# TCRT5000COM.net
KiCad netlist of a schematic drawn in Altium Designer
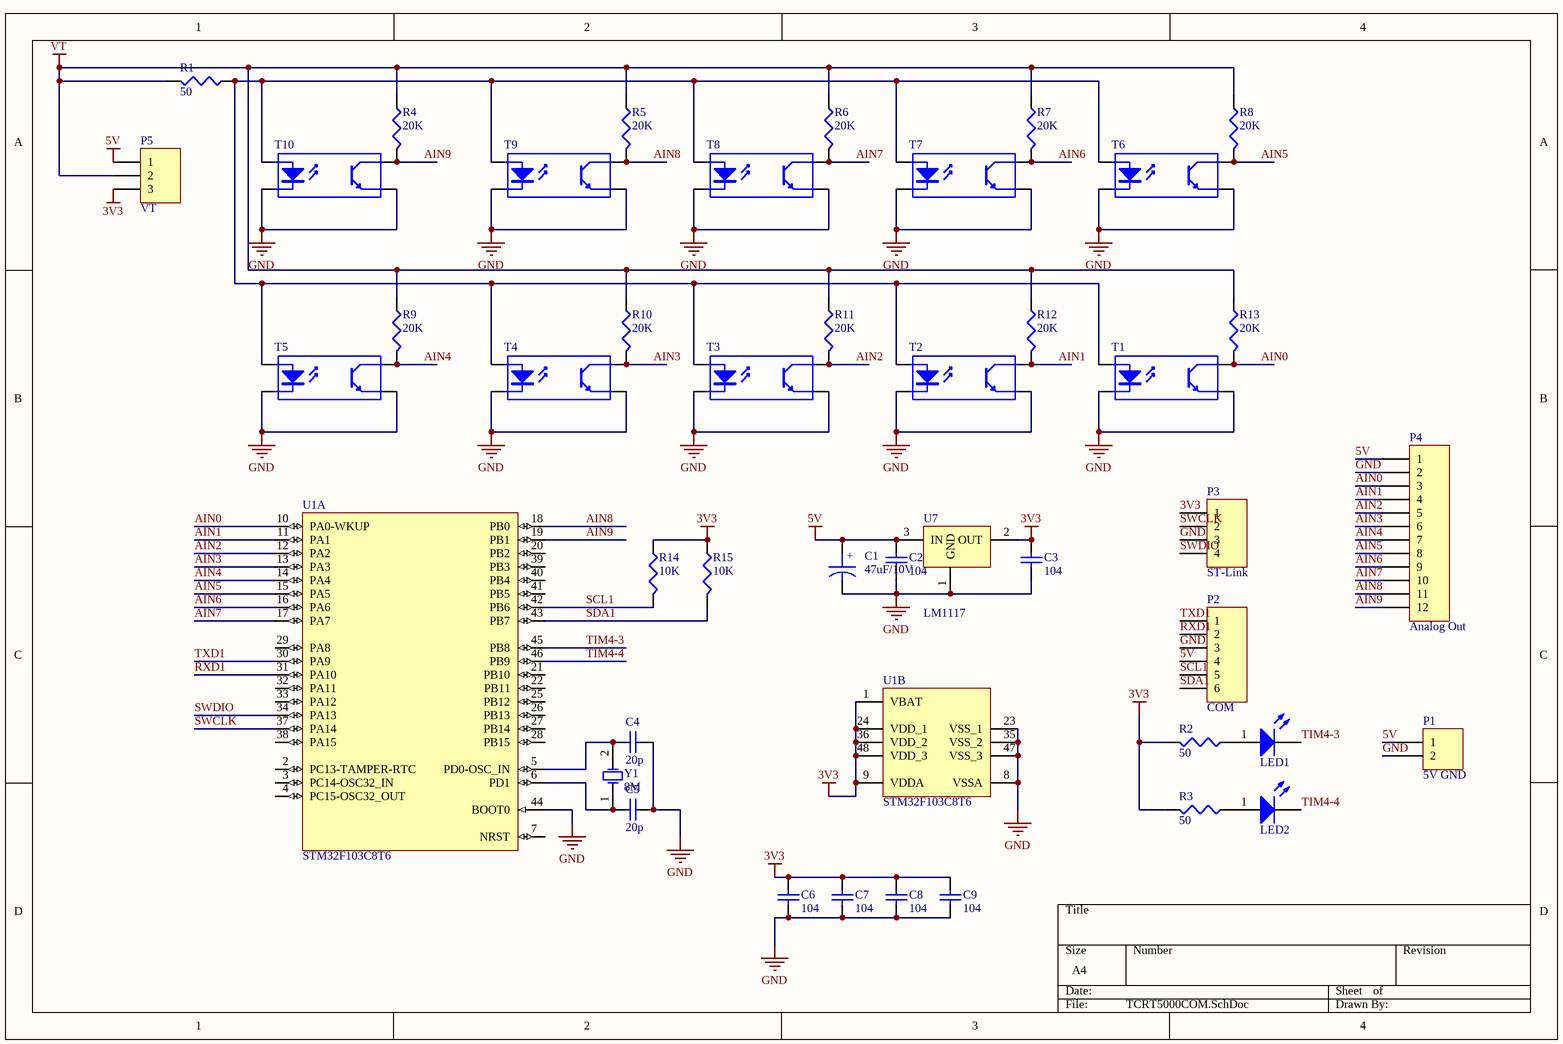
[diagram p0: TCRT5000COM.SchDoc]

(export (version "E")
  (design (tool "Eeschema 10.0.6"))
  (components
    (comp (ref "C1") (value "47uF/10V") (footprint "RB2") (libsource (lib "SmartHome") (part "CAP POL")))
    (comp (ref "C2")
      (value "104")
      (description "Capacitor")
      (fields (field (name "Comment") "Cap") (field (name "PUBLISHER") "Altium Limited"))
      (libsource (lib "Miscellaneous Devices") (part "Cap"))
    )
    (comp (ref "C3")
      (value "104")
      (description "Capacitor")
      (fields (field (name "Comment") "Cap") (field (name "PUBLISHER") "Altium Limited"))
      (libsource (lib "Miscellaneous Devices") (part "Cap"))
    )
    (comp (ref "C4")
      (value "20p")
      (footprint "0603")
      (description "Capacitor")
      (fields (field (name "PUBLISHER") "Altium Limited"))
      (libsource (lib "AMT149") (part "Cap"))
    )
    (comp (ref "C5")
      (value "20p")
      (footprint "0603")
      (description "Capacitor")
      (fields (field (name "PUBLISHER") "Altium Limited"))
      (libsource (lib "AMT149") (part "Cap"))
    )
    (comp (ref "C6")
      (value "104")
      (description "Capacitor")
      (fields (field (name "Comment") "Cap") (field (name "PUBLISHER") "Altium Limited"))
      (libsource (lib "Miscellaneous Devices") (part "Cap"))
    )
    (comp (ref "C7")
      (value "104")
      (description "Capacitor")
      (fields (field (name "Comment") "Cap") (field (name "PUBLISHER") "Altium Limited"))
      (libsource (lib "Miscellaneous Devices") (part "Cap"))
    )
    (comp (ref "C8")
      (value "104")
      (description "Capacitor")
      (fields (field (name "Comment") "Cap") (field (name "PUBLISHER") "Altium Limited"))
      (libsource (lib "Miscellaneous Devices") (part "Cap"))
    )
    (comp (ref "C9")
      (value "104")
      (description "Capacitor")
      (fields (field (name "Comment") "Cap") (field (name "PUBLISHER") "Altium Limited"))
      (libsource (lib "Miscellaneous Devices") (part "Cap"))
    )
    (comp (ref "LED1")
      (value "LED-white")
      (footprint "LED-white")
      (description "Typical INFRARED GaAs LED")
      (fields (field (name "PUBLISHER") "Altium Limited"))
      (libsource (lib "AMT149") (part "LED-white"))
    )
    (comp (ref "LED2")
      (value "LED-white")
      (footprint "LED-white")
      (description "Typical INFRARED GaAs LED")
      (fields (field (name "PUBLISHER") "Altium Limited"))
      (libsource (lib "AMT149") (part "LED-white"))
    )
    (comp (ref "P1")
      (value "5V GND")
      (footprint "SIP2-150")
      (description "Header, 2-Pin")
      (fields (field (name "PUBLISHER") "Altium Limited"))
      (libsource (lib "MainBoardV2") (part "Header 2"))
    )
    (comp (ref "P2")
      (value "COM")
      (footprint "HDR1X6")
      (description "Header, 6-Pin")
      (fields (field (name "PUBLISHER") "Altium Limited"))
      (libsource (lib "Miscellaneous Connectors") (part "Header 6"))
    )
    (comp (ref "P3")
      (value "ST-Link")
      (footprint "HDR1X4")
      (description "Header, 4-Pin")
      (fields (field (name "PUBLISHER") "Altium Limited"))
      (libsource (lib "Miscellaneous Connectors") (part "Header 4"))
    )
    (comp (ref "P4")
      (value "Analog Out")
      (footprint "HDR1X12")
      (description "Header, 12-Pin")
      (fields (field (name "PUBLISHER") "Altium Limited"))
      (libsource (lib "MainBoardV2") (part "Header 12"))
    )
    (comp (ref "P5")
      (value "VT")
      (footprint "HDR1X3")
      (description "Header, 3-Pin")
      (fields (field (name "PUBLISHER") "Altium Limited"))
      (libsource (lib "MainBoardV2") (part "Header 3"))
    )
    (comp (ref "R1")
      (value "50")
      (description "Resistor")
      (fields (field (name "Comment") "Res3") (field (name "PUBLISHER") "Altium Limited"))
      (libsource (lib "Miscellaneous Devices") (part "Res3"))
    )
    (comp (ref "R2")
      (value "50")
      (description "Resistor")
      (fields (field (name "Comment") "Res3") (field (name "PUBLISHER") "Altium Limited"))
      (libsource (lib "Miscellaneous Devices") (part "Res3"))
    )
    (comp (ref "R3")
      (value "50")
      (description "Resistor")
      (fields (field (name "Comment") "Res3") (field (name "PUBLISHER") "Altium Limited"))
      (libsource (lib "Miscellaneous Devices") (part "Res3"))
    )
    (comp (ref "R4")
      (value "20K")
      (description "Resistor")
      (fields (field (name "Comment") "Res3") (field (name "PUBLISHER") "Altium Limited"))
      (libsource (lib "Miscellaneous Devices") (part "Res3"))
    )
    (comp (ref "R5")
      (value "20K")
      (description "Resistor")
      (fields (field (name "Comment") "Res3") (field (name "PUBLISHER") "Altium Limited"))
      (libsource (lib "Miscellaneous Devices") (part "Res3"))
    )
    (comp (ref "R6")
      (value "20K")
      (description "Resistor")
      (fields (field (name "Comment") "Res3") (field (name "PUBLISHER") "Altium Limited"))
      (libsource (lib "Miscellaneous Devices") (part "Res3"))
    )
    (comp (ref "R7")
      (value "20K")
      (description "Resistor")
      (fields (field (name "Comment") "Res3") (field (name "PUBLISHER") "Altium Limited"))
      (libsource (lib "Miscellaneous Devices") (part "Res3"))
    )
    (comp (ref "R8")
      (value "20K")
      (description "Resistor")
      (fields (field (name "Comment") "Res3") (field (name "PUBLISHER") "Altium Limited"))
      (libsource (lib "Miscellaneous Devices") (part "Res3"))
    )
    (comp (ref "R9")
      (value "20K")
      (description "Resistor")
      (fields (field (name "Comment") "Res3") (field (name "PUBLISHER") "Altium Limited"))
      (libsource (lib "Miscellaneous Devices") (part "Res3"))
    )
    (comp (ref "R10")
      (value "20K")
      (description "Resistor")
      (fields (field (name "Comment") "Res3") (field (name "PUBLISHER") "Altium Limited"))
      (libsource (lib "Miscellaneous Devices") (part "Res3"))
    )
    (comp (ref "R11")
      (value "20K")
      (description "Resistor")
      (fields (field (name "Comment") "Res3") (field (name "PUBLISHER") "Altium Limited"))
      (libsource (lib "Miscellaneous Devices") (part "Res3"))
    )
    (comp (ref "R12")
      (value "20K")
      (description "Resistor")
      (fields (field (name "Comment") "Res3") (field (name "PUBLISHER") "Altium Limited"))
      (libsource (lib "Miscellaneous Devices") (part "Res3"))
    )
    (comp (ref "R13")
      (value "20K")
      (description "Resistor")
      (fields (field (name "Comment") "Res3") (field (name "PUBLISHER") "Altium Limited"))
      (libsource (lib "Miscellaneous Devices") (part "Res3"))
    )
    (comp (ref "R14")
      (value "10K")
      (description "Resistor")
      (fields (field (name "Comment") "Res3") (field (name "PUBLISHER") "Altium Limited"))
      (libsource (lib "Miscellaneous Devices") (part "Res3"))
    )
    (comp (ref "R15")
      (value "10K")
      (description "Resistor")
      (fields (field (name "Comment") "Res3") (field (name "PUBLISHER") "Altium Limited"))
      (libsource (lib "Miscellaneous Devices") (part "Res3"))
    )
    (comp (ref "T1")
      (value "Optoisolator1")
      (footprint "TCRT5000")
      (description "4-Pin Phototransistor Optocoupler")
      (fields (field (name "PUBLISHER") "Altium Limited"))
      (libsource (lib "Miscellaneous Devices") (part "Optoisolator1"))
    )
    (comp (ref "T2")
      (value "Optoisolator1")
      (footprint "TCRT5000")
      (description "4-Pin Phototransistor Optocoupler")
      (fields (field (name "PUBLISHER") "Altium Limited"))
      (libsource (lib "Miscellaneous Devices") (part "Optoisolator1"))
    )
    (comp (ref "T3")
      (value "Optoisolator1")
      (footprint "TCRT5000")
      (description "4-Pin Phototransistor Optocoupler")
      (fields (field (name "PUBLISHER") "Altium Limited"))
      (libsource (lib "Miscellaneous Devices") (part "Optoisolator1"))
    )
    (comp (ref "T4")
      (value "Optoisolator1")
      (footprint "TCRT5000")
      (description "4-Pin Phototransistor Optocoupler")
      (fields (field (name "PUBLISHER") "Altium Limited"))
      (libsource (lib "Miscellaneous Devices") (part "Optoisolator1"))
    )
    (comp (ref "T5")
      (value "Optoisolator1")
      (footprint "TCRT5000")
      (description "4-Pin Phototransistor Optocoupler")
      (fields (field (name "PUBLISHER") "Altium Limited"))
      (libsource (lib "Miscellaneous Devices") (part "Optoisolator1"))
    )
    (comp (ref "T6")
      (value "Optoisolator1")
      (footprint "TCRT5000")
      (description "4-Pin Phototransistor Optocoupler")
      (fields (field (name "PUBLISHER") "Altium Limited"))
      (libsource (lib "Miscellaneous Devices") (part "Optoisolator1"))
    )
    (comp (ref "T7")
      (value "Optoisolator1")
      (footprint "TCRT5000")
      (description "4-Pin Phototransistor Optocoupler")
      (fields (field (name "PUBLISHER") "Altium Limited"))
      (libsource (lib "Miscellaneous Devices") (part "Optoisolator1"))
    )
    (comp (ref "T8")
      (value "Optoisolator1")
      (footprint "TCRT5000")
      (description "4-Pin Phototransistor Optocoupler")
      (fields (field (name "PUBLISHER") "Altium Limited"))
      (libsource (lib "Miscellaneous Devices") (part "Optoisolator1"))
    )
    (comp (ref "T9")
      (value "Optoisolator1")
      (footprint "TCRT5000")
      (description "4-Pin Phototransistor Optocoupler")
      (fields (field (name "PUBLISHER") "Altium Limited"))
      (libsource (lib "Miscellaneous Devices") (part "Optoisolator1"))
    )
    (comp (ref "T10")
      (value "Optoisolator1")
      (footprint "TCRT5000")
      (description "4-Pin Phototransistor Optocoupler")
      (fields (field (name "PUBLISHER") "Altium Limited"))
      (libsource (lib "Miscellaneous Devices") (part "Optoisolator1"))
    )
    (comp (ref "U1")
      (value "STM32F103C8T6")
      (footprint "QUAD48")
      (libsource (lib "AMT149") (part "STM32F103C8T6"))
    )
    (comp (ref "U7") (value "LM1117") (footprint "SPP3") (libsource (lib "*") (part "LM1117")))
    (comp (ref "Y1")
      (value "8M")
      (footprint "XTAL1")
      (description "Crystal Oscillator")
      (fields (field (name "PUBLISHER") "Altium Limited"))
      (libsource (lib "AMT149") (part "XTAL"))
    )
  )
  (nets
    (net (code "1") (name "/AIN0") (class "Default")
      (node (ref "P4") (pin "3") (pinfunction "3_3") (pintype "passive"))
      (node (ref "R13") (pin "2") (pinfunction "2_2") (pintype "passive"))
      (node (ref "T1") (pin "4") (pinfunction "C_4") (pintype "passive"))
      (node (ref "U1") (pin "10") (pinfunction "PA0-WKUP_10") (pintype "bidirectional"))
    )
    (net (code "2") (name "/AIN1") (class "Default")
      (node (ref "P4") (pin "4") (pinfunction "4_4") (pintype "passive"))
      (node (ref "R12") (pin "2") (pinfunction "2_2") (pintype "passive"))
      (node (ref "T2") (pin "4") (pinfunction "C_4") (pintype "passive"))
      (node (ref "U1") (pin "11") (pinfunction "PA1_11") (pintype "bidirectional"))
    )
    (net (code "3") (name "/AIN2") (class "Default")
      (node (ref "P4") (pin "5") (pinfunction "5_5") (pintype "passive"))
      (node (ref "R11") (pin "2") (pinfunction "2_2") (pintype "passive"))
      (node (ref "T3") (pin "4") (pinfunction "C_4") (pintype "passive"))
      (node (ref "U1") (pin "12") (pinfunction "PA2_12") (pintype "bidirectional"))
    )
    (net (code "4") (name "/AIN3") (class "Default")
      (node (ref "P4") (pin "6") (pinfunction "6_6") (pintype "passive"))
      (node (ref "R10") (pin "2") (pinfunction "2_2") (pintype "passive"))
      (node (ref "T4") (pin "4") (pinfunction "C_4") (pintype "passive"))
      (node (ref "U1") (pin "13") (pinfunction "PA3_13") (pintype "bidirectional"))
    )
    (net (code "5") (name "/AIN4") (class "Default")
      (node (ref "P4") (pin "7") (pinfunction "7_7") (pintype "passive"))
      (node (ref "R9") (pin "2") (pinfunction "2_2") (pintype "passive"))
      (node (ref "T5") (pin "4") (pinfunction "C_4") (pintype "passive"))
      (node (ref "U1") (pin "14") (pinfunction "PA4_14") (pintype "bidirectional"))
    )
    (net (code "6") (name "/AIN5") (class "Default")
      (node (ref "P4") (pin "8") (pinfunction "8_8") (pintype "passive"))
      (node (ref "R8") (pin "2") (pinfunction "2_2") (pintype "passive"))
      (node (ref "T6") (pin "4") (pinfunction "C_4") (pintype "passive"))
      (node (ref "U1") (pin "15") (pinfunction "PA5_15") (pintype "bidirectional"))
    )
    (net (code "7") (name "/AIN6") (class "Default")
      (node (ref "P4") (pin "9") (pinfunction "9_9") (pintype "passive"))
      (node (ref "R7") (pin "2") (pinfunction "2_2") (pintype "passive"))
      (node (ref "T7") (pin "4") (pinfunction "C_4") (pintype "passive"))
      (node (ref "U1") (pin "16") (pinfunction "PA6_16") (pintype "bidirectional"))
    )
    (net (code "8") (name "/AIN7") (class "Default")
      (node (ref "P4") (pin "10") (pinfunction "10_10") (pintype "passive"))
      (node (ref "R6") (pin "2") (pinfunction "2_2") (pintype "passive"))
      (node (ref "T8") (pin "4") (pinfunction "C_4") (pintype "passive"))
      (node (ref "U1") (pin "17") (pinfunction "PA7_17") (pintype "bidirectional"))
    )
    (net (code "9") (name "/AIN8") (class "Default")
      (node (ref "P4") (pin "11") (pinfunction "11_11") (pintype "passive"))
      (node (ref "R5") (pin "2") (pinfunction "2_2") (pintype "passive"))
      (node (ref "T9") (pin "4") (pinfunction "C_4") (pintype "passive"))
      (node (ref "U1") (pin "18") (pinfunction "PB0_18") (pintype "bidirectional"))
    )
    (net (code "10") (name "/AIN9") (class "Default")
      (node (ref "P4") (pin "12") (pinfunction "12_12") (pintype "passive"))
      (node (ref "R4") (pin "2") (pinfunction "2_2") (pintype "passive"))
      (node (ref "T10") (pin "4") (pinfunction "C_4") (pintype "passive"))
      (node (ref "U1") (pin "19") (pinfunction "PB1_19") (pintype "bidirectional"))
    )
    (net (code "11") (name "/RXD1") (class "Default")
      (node (ref "P2") (pin "2") (pinfunction "2_2") (pintype "passive"))
      (node (ref "U1") (pin "31") (pinfunction "PA10_31") (pintype "bidirectional"))
    )
    (net (code "12") (name "/SCL1") (class "Default")
      (node (ref "P2") (pin "5") (pinfunction "5_5") (pintype "passive"))
      (node (ref "R14") (pin "2") (pinfunction "2_2") (pintype "passive"))
      (node (ref "U1") (pin "42") (pinfunction "PB6_42") (pintype "bidirectional"))
    )
    (net (code "13") (name "/SDA1") (class "Default")
      (node (ref "P2") (pin "6") (pinfunction "6_6") (pintype "passive"))
      (node (ref "R15") (pin "2") (pinfunction "2_2") (pintype "passive"))
      (node (ref "U1") (pin "43") (pinfunction "PB7_43") (pintype "bidirectional"))
    )
    (net (code "14") (name "/SWCLK") (class "Default")
      (node (ref "P3") (pin "2") (pinfunction "2_2") (pintype "passive"))
      (node (ref "U1") (pin "37") (pinfunction "PA14_37") (pintype "bidirectional"))
    )
    (net (code "15") (name "/SWDIO") (class "Default")
      (node (ref "P3") (pin "4") (pinfunction "4_4") (pintype "passive"))
      (node (ref "U1") (pin "34") (pinfunction "PA13_34") (pintype "bidirectional"))
    )
    (net (code "16") (name "/TIM4-3") (class "Default")
      (node (ref "LED1") (pin "2") (pinfunction "K_2") (pintype "passive"))
      (node (ref "U1") (pin "45") (pinfunction "PB8_45") (pintype "bidirectional"))
    )
    (net (code "17") (name "/TIM4-4") (class "Default")
      (node (ref "LED2") (pin "2") (pinfunction "K_2") (pintype "passive"))
      (node (ref "U1") (pin "46") (pinfunction "PB9_46") (pintype "bidirectional"))
    )
    (net (code "18") (name "/TXD1") (class "Default")
      (node (ref "P2") (pin "1") (pinfunction "1_1") (pintype "passive"))
      (node (ref "U1") (pin "30") (pinfunction "PA9_30") (pintype "bidirectional"))
    )
    (net (code "19") (name "3V3") (class "Default")
      (node (ref "C3") (pin "2") (pinfunction "2_2") (pintype "passive"))
      (node (ref "C6") (pin "2") (pinfunction "2_2") (pintype "passive"))
      (node (ref "C7") (pin "2") (pinfunction "2_2") (pintype "passive"))
      (node (ref "C8") (pin "2") (pinfunction "2_2") (pintype "passive"))
      (node (ref "C9") (pin "2") (pinfunction "2_2") (pintype "passive"))
      (node (ref "P3") (pin "1") (pinfunction "1_1") (pintype "passive"))
      (node (ref "P5") (pin "3") (pinfunction "3_3") (pintype "passive"))
      (node (ref "R14") (pin "1") (pinfunction "1_1") (pintype "passive"))
      (node (ref "R15") (pin "1") (pinfunction "1_1") (pintype "passive"))
      (node (ref "R2") (pin "2") (pinfunction "2_2") (pintype "passive"))
      (node (ref "R3") (pin "2") (pinfunction "2_2") (pintype "passive"))
      (node (ref "U1") (pin "1") (pinfunction "VBAT_1") (pintype "power_in"))
      (node (ref "U1") (pin "24") (pinfunction "VDD_1_24") (pintype "power_in"))
      (node (ref "U1") (pin "36") (pinfunction "VDD_2_36") (pintype "power_in"))
      (node (ref "U1") (pin "48") (pinfunction "VDD_3_48") (pintype "power_in"))
      (node (ref "U1") (pin "9") (pinfunction "VDDA_9") (pintype "power_in"))
      (node (ref "U7") (pin "2") (pinfunction "OUT_2") (pintype "passive"))
    )
    (net (code "20") (name "5V") (class "Default")
      (node (ref "C1") (pin "1") (pinfunction "1_1") (pintype "passive"))
      (node (ref "C2") (pin "2") (pinfunction "2_2") (pintype "passive"))
      (node (ref "P1") (pin "1") (pinfunction "1_1") (pintype "passive"))
      (node (ref "P2") (pin "4") (pinfunction "4_4") (pintype "passive"))
      (node (ref "P4") (pin "1") (pinfunction "1_1") (pintype "passive"))
      (node (ref "P5") (pin "1") (pinfunction "1_1") (pintype "passive"))
      (node (ref "U7") (pin "3") (pinfunction "IN_3") (pintype "passive"))
    )
    (net (code "21") (name "GND") (class "Default")
      (node (ref "C1") (pin "2") (pinfunction "2_2") (pintype "passive"))
      (node (ref "C2") (pin "1") (pinfunction "1_1") (pintype "passive"))
      (node (ref "C3") (pin "1") (pinfunction "1_1") (pintype "passive"))
      (node (ref "C4") (pin "2") (pinfunction "2_2") (pintype "passive"))
      (node (ref "C5") (pin "2") (pinfunction "2_2") (pintype "passive"))
      (node (ref "C6") (pin "1") (pinfunction "1_1") (pintype "passive"))
      (node (ref "C7") (pin "1") (pinfunction "1_1") (pintype "passive"))
      (node (ref "C8") (pin "1") (pinfunction "1_1") (pintype "passive"))
      (node (ref "C9") (pin "1") (pinfunction "1_1") (pintype "passive"))
      (node (ref "P1") (pin "2") (pinfunction "2_2") (pintype "passive"))
      (node (ref "P2") (pin "3") (pinfunction "3_3") (pintype "passive"))
      (node (ref "P3") (pin "3") (pinfunction "3_3") (pintype "passive"))
      (node (ref "P4") (pin "2") (pinfunction "2_2") (pintype "passive"))
      (node (ref "T1") (pin "2") (pinfunction "K_2") (pintype "passive"))
      (node (ref "T1") (pin "3") (pinfunction "E_3") (pintype "passive"))
      (node (ref "T10") (pin "2") (pinfunction "K_2") (pintype "passive"))
      (node (ref "T10") (pin "3") (pinfunction "E_3") (pintype "passive"))
      (node (ref "T2") (pin "2") (pinfunction "K_2") (pintype "passive"))
      (node (ref "T2") (pin "3") (pinfunction "E_3") (pintype "passive"))
      (node (ref "T3") (pin "2") (pinfunction "K_2") (pintype "passive"))
      (node (ref "T3") (pin "3") (pinfunction "E_3") (pintype "passive"))
      (node (ref "T4") (pin "2") (pinfunction "K_2") (pintype "passive"))
      (node (ref "T4") (pin "3") (pinfunction "E_3") (pintype "passive"))
      (node (ref "T5") (pin "2") (pinfunction "K_2") (pintype "passive"))
      (node (ref "T5") (pin "3") (pinfunction "E_3") (pintype "passive"))
      (node (ref "T6") (pin "2") (pinfunction "K_2") (pintype "passive"))
      (node (ref "T6") (pin "3") (pinfunction "E_3") (pintype "passive"))
      (node (ref "T7") (pin "2") (pinfunction "K_2") (pintype "passive"))
      (node (ref "T7") (pin "3") (pinfunction "E_3") (pintype "passive"))
      (node (ref "T8") (pin "2") (pinfunction "K_2") (pintype "passive"))
      (node (ref "T8") (pin "3") (pinfunction "E_3") (pintype "passive"))
      (node (ref "T9") (pin "2") (pinfunction "K_2") (pintype "passive"))
      (node (ref "T9") (pin "3") (pinfunction "E_3") (pintype "passive"))
      (node (ref "U1") (pin "23") (pinfunction "VSS_1_23") (pintype "power_in"))
      (node (ref "U1") (pin "35") (pinfunction "VSS_2_35") (pintype "power_in"))
      (node (ref "U1") (pin "44") (pinfunction "BOOT0_44") (pintype "input"))
      (node (ref "U1") (pin "47") (pinfunction "VSS_3_47") (pintype "power_in"))
      (node (ref "U1") (pin "8") (pinfunction "VSSA_8") (pintype "power_in"))
      (node (ref "U7") (pin "1") (pinfunction "GND_1") (pintype "passive"))
    )
    (net (code "22") (name "Net-(LED1-A)") (class "Default")
      (node (ref "LED1") (pin "1") (pinfunction "A_1") (pintype "passive"))
      (node (ref "R2") (pin "1") (pinfunction "1_1") (pintype "passive"))
    )
    (net (code "23") (name "Net-(LED2-A)") (class "Default")
      (node (ref "LED2") (pin "1") (pinfunction "A_1") (pintype "passive"))
      (node (ref "R3") (pin "1") (pinfunction "1_1") (pintype "passive"))
    )
    (net (code "24") (name "Net-(T1-A)") (class "Default")
      (node (ref "R1") (pin "1") (pinfunction "1_1") (pintype "passive"))
      (node (ref "T1") (pin "1") (pinfunction "A_1") (pintype "passive"))
      (node (ref "T10") (pin "1") (pinfunction "A_1") (pintype "passive"))
      (node (ref "T2") (pin "1") (pinfunction "A_1") (pintype "passive"))
      (node (ref "T3") (pin "1") (pinfunction "A_1") (pintype "passive"))
      (node (ref "T4") (pin "1") (pinfunction "A_1") (pintype "passive"))
      (node (ref "T5") (pin "1") (pinfunction "A_1") (pintype "passive"))
      (node (ref "T6") (pin "1") (pinfunction "A_1") (pintype "passive"))
      (node (ref "T7") (pin "1") (pinfunction "A_1") (pintype "passive"))
      (node (ref "T8") (pin "1") (pinfunction "A_1") (pintype "passive"))
      (node (ref "T9") (pin "1") (pinfunction "A_1") (pintype "passive"))
    )
    (net (code "25") (name "Net-(U1A-PD0-OSC_IN)") (class "Default")
      (node (ref "C4") (pin "1") (pinfunction "1_1") (pintype "passive"))
      (node (ref "U1") (pin "5") (pinfunction "PD0-OSC_IN_5") (pintype "bidirectional"))
      (node (ref "Y1") (pin "2") (pinfunction "OSC2_2") (pintype "passive"))
    )
    (net (code "26") (name "Net-(U1A-PD1)") (class "Default")
      (node (ref "C5") (pin "1") (pinfunction "1_1") (pintype "passive"))
      (node (ref "U1") (pin "6") (pinfunction "PD1_6") (pintype "bidirectional"))
      (node (ref "Y1") (pin "1") (pinfunction "OSC1_1") (pintype "passive"))
    )
    (net (code "27") (name "VT") (class "Default")
      (node (ref "P5") (pin "2") (pinfunction "2_2") (pintype "passive"))
      (node (ref "R1") (pin "2") (pinfunction "2_2") (pintype "passive"))
      (node (ref "R10") (pin "1") (pinfunction "1_1") (pintype "passive"))
      (node (ref "R11") (pin "1") (pinfunction "1_1") (pintype "passive"))
      (node (ref "R12") (pin "1") (pinfunction "1_1") (pintype "passive"))
      (node (ref "R13") (pin "1") (pinfunction "1_1") (pintype "passive"))
      (node (ref "R4") (pin "1") (pinfunction "1_1") (pintype "passive"))
      (node (ref "R5") (pin "1") (pinfunction "1_1") (pintype "passive"))
      (node (ref "R6") (pin "1") (pinfunction "1_1") (pintype "passive"))
      (node (ref "R7") (pin "1") (pinfunction "1_1") (pintype "passive"))
      (node (ref "R8") (pin "1") (pinfunction "1_1") (pintype "passive"))
      (node (ref "R9") (pin "1") (pinfunction "1_1") (pintype "passive"))
    )
    (net (code "28") (name "unconnected-(U1A-NRST-Pad7)") (class "Default")
      (node (ref "U1") (pin "7") (pinfunction "NRST_7") (pintype "bidirectional"))
    )
    (net (code "29") (name "unconnected-(U1A-PA8-Pad29)") (class "Default")
      (node (ref "U1") (pin "29") (pinfunction "PA8_29") (pintype "bidirectional"))
    )
    (net (code "30") (name "unconnected-(U1A-PA11-Pad32)") (class "Default")
      (node (ref "U1") (pin "32") (pinfunction "PA11_32") (pintype "bidirectional"))
    )
    (net (code "31") (name "unconnected-(U1A-PA12-Pad33)") (class "Default")
      (node (ref "U1") (pin "33") (pinfunction "PA12_33") (pintype "bidirectional"))
    )
    (net (code "32") (name "unconnected-(U1A-PA15-Pad38)") (class "Default")
      (node (ref "U1") (pin "38") (pinfunction "PA15_38") (pintype "bidirectional"))
    )
    (net (code "33") (name "unconnected-(U1A-PB2-Pad20)") (class "Default")
      (node (ref "U1") (pin "20") (pinfunction "PB2_20") (pintype "bidirectional"))
    )
    (net (code "34") (name "unconnected-(U1A-PB3-Pad39)") (class "Default")
      (node (ref "U1") (pin "39") (pinfunction "PB3_39") (pintype "bidirectional"))
    )
    (net (code "35") (name "unconnected-(U1A-PB4-Pad40)") (class "Default")
      (node (ref "U1") (pin "40") (pinfunction "PB4_40") (pintype "bidirectional"))
    )
    (net (code "36") (name "unconnected-(U1A-PB5-Pad41)") (class "Default")
      (node (ref "U1") (pin "41") (pinfunction "PB5_41") (pintype "bidirectional"))
    )
    (net (code "37") (name "unconnected-(U1A-PB10-Pad21)") (class "Default")
      (node (ref "U1") (pin "21") (pinfunction "PB10_21") (pintype "bidirectional"))
    )
    (net (code "38") (name "unconnected-(U1A-PB11-Pad22)") (class "Default")
      (node (ref "U1") (pin "22") (pinfunction "PB11_22") (pintype "bidirectional"))
    )
    (net (code "39") (name "unconnected-(U1A-PB12-Pad25)") (class "Default")
      (node (ref "U1") (pin "25") (pinfunction "PB12_25") (pintype "bidirectional"))
    )
    (net (code "40") (name "unconnected-(U1A-PB13-Pad26)") (class "Default")
      (node (ref "U1") (pin "26") (pinfunction "PB13_26") (pintype "bidirectional"))
    )
    (net (code "41") (name "unconnected-(U1A-PB14-Pad27)") (class "Default")
      (node (ref "U1") (pin "27") (pinfunction "PB14_27") (pintype "bidirectional"))
    )
    (net (code "42") (name "unconnected-(U1A-PB15-Pad28)") (class "Default")
      (node (ref "U1") (pin "28") (pinfunction "PB15_28") (pintype "bidirectional"))
    )
    (net (code "43") (name "unconnected-(U1A-PC13-TAMPER-RTC-Pad2)") (class "Default")
      (node (ref "U1") (pin "2") (pinfunction "PC13-TAMPER-RTC_2") (pintype "bidirectional"))
    )
    (net (code "44") (name "unconnected-(U1A-PC14-OSC32_IN-Pad3)") (class "Default")
      (node (ref "U1") (pin "3") (pinfunction "PC14-OSC32_IN_3") (pintype "bidirectional"))
    )
    (net (code "45") (name "unconnected-(U1A-PC15-OSC32_OUT-Pad4)") (class "Default")
      (node (ref "U1") (pin "4") (pinfunction "PC15-OSC32_OUT_4") (pintype "bidirectional"))
    )
  )
)
